# 6_-H3_MAIN.net
KiCad netlist of a schematic drawn in Altium Designer
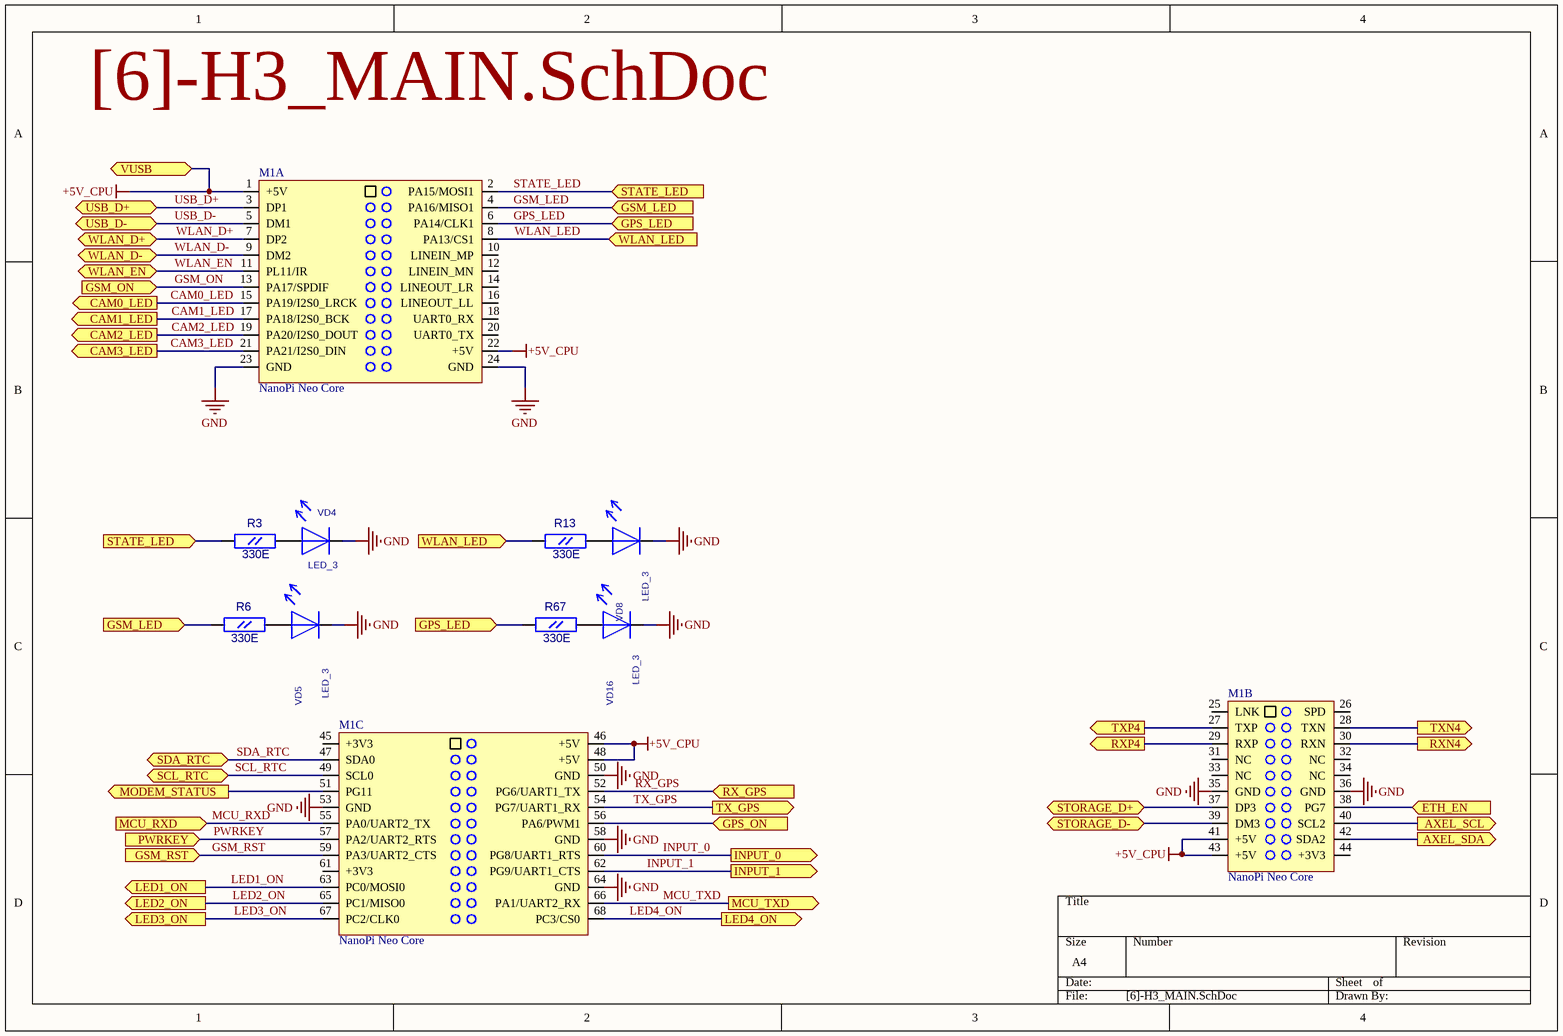
[diagram p0: [6]-H3_MAIN.SchDoc]

(export (version "E")
  (design (tool "Eeschema 10.0.6"))
  (components
    (comp (ref "M1")
      (value "NanoPi Neo Core")
      (footprint "NanoPiNeo_CORE")
      (description "Nano Pi Neo Core Allwinner H3 based embedded module")
      (libsource (lib "fizik_lib") (part "NanoPi Neo Core"))
    )
    (comp (ref "R3")
      (value "330E")
      (footprint "RC0603")
      (description "RC0603")
      (libsource (lib "fizik_lib (1)") (part "RC0603"))
    )
    (comp (ref "R6")
      (value "330E")
      (footprint "RC0603")
      (description "RC0603")
      (libsource (lib "fizik_lib (1)") (part "RC0603"))
    )
    (comp (ref "R13")
      (value "330E")
      (footprint "RC0603")
      (description "RC0603")
      (libsource (lib "fizik_lib (1)") (part "RC0603"))
    )
    (comp (ref "R67")
      (value "330E")
      (footprint "RC0603")
      (description "RC0603")
      (libsource (lib "fizik_lib (1)") (part "RC0603"))
    )
    (comp (ref "VD4") (value "LED_3") (footprint "LED3") (libsource (lib "fizik_lib (1)") (part "LED_3")))
    (comp (ref "VD5") (value "LED_3") (footprint "LED3") (libsource (lib "fizik_lib (1)") (part "LED_3")))
    (comp (ref "VD8") (value "LED_3") (footprint "LED3") (libsource (lib "fizik_lib (1)") (part "LED_3")))
    (comp (ref "VD16") (value "LED_3") (footprint "LED3") (libsource (lib "fizik_lib (1)") (part "LED_3")))
  )
  (nets
    (net (code "1") (name "+5V_CPU") (class "Default")
      (node (ref "M1") (pin "1") (pinfunction "+5V_1") (pintype "passive"))
      (node (ref "M1") (pin "22") (pinfunction "+5V_22") (pintype "passive"))
      (node (ref "M1") (pin "41") (pinfunction "+5V_41") (pintype "passive"))
      (node (ref "M1") (pin "43") (pinfunction "+5V_43") (pintype "passive"))
      (node (ref "M1") (pin "46") (pinfunction "+5V_46") (pintype "passive"))
      (node (ref "M1") (pin "48") (pinfunction "+5V_48") (pintype "passive"))
    )
    (net (code "2") (name "/AXEL_SCL") (class "Default")
      (node (ref "M1") (pin "40") (pinfunction "SCL2_40") (pintype "passive"))
    )
    (net (code "3") (name "/AXEL_SDA") (class "Default")
      (node (ref "M1") (pin "42") (pinfunction "SDA2_42") (pintype "passive"))
    )
    (net (code "4") (name "/CAM0_LED") (class "Default")
      (node (ref "M1") (pin "15") (pinfunction "PA19/I2S0_LRCK_15") (pintype "passive"))
    )
    (net (code "5") (name "/CAM1_LED") (class "Default")
      (node (ref "M1") (pin "17") (pinfunction "PA18/I2S0_BCK_17") (pintype "passive"))
    )
    (net (code "6") (name "/CAM2_LED") (class "Default")
      (node (ref "M1") (pin "19") (pinfunction "PA20/I2S0_DOUT_19") (pintype "passive"))
    )
    (net (code "7") (name "/CAM3_LED") (class "Default")
      (node (ref "M1") (pin "21") (pinfunction "PA21/I2S0_DIN_21") (pintype "passive"))
    )
    (net (code "8") (name "/ETH_EN") (class "Default")
      (node (ref "M1") (pin "38") (pinfunction "PG7_38") (pintype "passive"))
    )
    (net (code "9") (name "/GPS_LED") (class "Default")
      (node (ref "M1") (pin "6") (pinfunction "PA14/CLK1_6") (pintype "passive"))
      (node (ref "R67") (pin "1") (pinfunction "A_1") (pintype "passive"))
    )
    (net (code "10") (name "/GPS_ON") (class "Default")
      (node (ref "M1") (pin "56") (pinfunction "PA6/PWM1_56") (pintype "passive"))
    )
    (net (code "11") (name "/GSM_LED") (class "Default")
      (node (ref "M1") (pin "4") (pinfunction "PA16/MISO1_4") (pintype "passive"))
      (node (ref "R6") (pin "1") (pinfunction "A_1") (pintype "passive"))
    )
    (net (code "12") (name "/GSM_ON") (class "Default")
      (node (ref "M1") (pin "13") (pinfunction "PA17/SPDIF_13") (pintype "passive"))
    )
    (net (code "13") (name "/GSM_RST") (class "Default")
      (node (ref "M1") (pin "59") (pinfunction "PA3/UART2_CTS_59") (pintype "passive"))
    )
    (net (code "14") (name "/INPUT_0") (class "Default")
      (node (ref "M1") (pin "60") (pinfunction "PG8/UART1_RTS_60") (pintype "passive"))
    )
    (net (code "15") (name "/INPUT_1") (class "Default")
      (node (ref "M1") (pin "62") (pinfunction "PG9/UART1_CTS_62") (pintype "passive"))
    )
    (net (code "16") (name "/LED1_ON") (class "Default")
      (node (ref "M1") (pin "63") (pinfunction "PC0/MOSI0_63") (pintype "passive"))
    )
    (net (code "17") (name "/LED2_ON") (class "Default")
      (node (ref "M1") (pin "65") (pinfunction "PC1/MISO0_65") (pintype "passive"))
    )
    (net (code "18") (name "/LED3_ON") (class "Default")
      (node (ref "M1") (pin "67") (pinfunction "PC2/CLK0_67") (pintype "passive"))
    )
    (net (code "19") (name "/LED4_ON") (class "Default")
      (node (ref "M1") (pin "68") (pinfunction "PC3/CS0_68") (pintype "passive"))
    )
    (net (code "20") (name "/MCU_RXD") (class "Default")
      (node (ref "M1") (pin "55") (pinfunction "PA0/UART2_TX_55") (pintype "passive"))
    )
    (net (code "21") (name "/MCU_TXD") (class "Default")
      (node (ref "M1") (pin "66") (pinfunction "PA1/UART2_RX_66") (pintype "passive"))
    )
    (net (code "22") (name "/MODEM_STATUS") (class "Default")
      (node (ref "M1") (pin "51") (pinfunction "PG11_51") (pintype "passive"))
    )
    (net (code "23") (name "/PWRKEY") (class "Default")
      (node (ref "M1") (pin "57") (pinfunction "PA2/UART2_RTS_57") (pintype "passive"))
    )
    (net (code "24") (name "/RXN4") (class "Default")
      (node (ref "M1") (pin "30") (pinfunction "RXN_30") (pintype "passive"))
    )
    (net (code "25") (name "/RXP4") (class "Default")
      (node (ref "M1") (pin "29") (pinfunction "RXP_29") (pintype "passive"))
    )
    (net (code "26") (name "/RX_GPS") (class "Default")
      (node (ref "M1") (pin "52") (pinfunction "PG6/UART1_TX_52") (pintype "passive"))
    )
    (net (code "27") (name "/SCL_RTC") (class "Default")
      (node (ref "M1") (pin "49") (pinfunction "SCL0_49") (pintype "passive"))
    )
    (net (code "28") (name "/SDA_RTC") (class "Default")
      (node (ref "M1") (pin "47") (pinfunction "SDA0_47") (pintype "passive"))
    )
    (net (code "29") (name "/STATE_LED") (class "Default")
      (node (ref "M1") (pin "2") (pinfunction "PA15/MOSI1_2") (pintype "passive"))
      (node (ref "R3") (pin "1") (pinfunction "A_1") (pintype "passive"))
    )
    (net (code "30") (name "/STORAGE_D+") (class "Default")
      (node (ref "M1") (pin "37") (pinfunction "DP3_37") (pintype "passive"))
    )
    (net (code "31") (name "/STORAGE_D-") (class "Default")
      (node (ref "M1") (pin "39") (pinfunction "DM3_39") (pintype "passive"))
    )
    (net (code "32") (name "/TXN4") (class "Default")
      (node (ref "M1") (pin "28") (pinfunction "TXN_28") (pintype "passive"))
    )
    (net (code "33") (name "/TXP4") (class "Default")
      (node (ref "M1") (pin "27") (pinfunction "TXP_27") (pintype "passive"))
    )
    (net (code "34") (name "/TX_GPS") (class "Default")
      (node (ref "M1") (pin "54") (pinfunction "PG7/UART1_RX_54") (pintype "passive"))
    )
    (net (code "35") (name "/USB_D+") (class "Default")
      (node (ref "M1") (pin "3") (pinfunction "DP1_3") (pintype "passive"))
    )
    (net (code "36") (name "/USB_D-") (class "Default")
      (node (ref "M1") (pin "5") (pinfunction "DM1_5") (pintype "passive"))
    )
    (net (code "37") (name "/WLAN_D+") (class "Default")
      (node (ref "M1") (pin "7") (pinfunction "DP2_7") (pintype "passive"))
    )
    (net (code "38") (name "/WLAN_D-") (class "Default")
      (node (ref "M1") (pin "9") (pinfunction "DM2_9") (pintype "passive"))
    )
    (net (code "39") (name "/WLAN_EN") (class "Default")
      (node (ref "M1") (pin "11") (pinfunction "PL11/IR_11") (pintype "passive"))
    )
    (net (code "40") (name "/WLAN_LED") (class "Default")
      (node (ref "M1") (pin "8") (pinfunction "PA13/CS1_8") (pintype "passive"))
      (node (ref "R13") (pin "1") (pinfunction "A_1") (pintype "passive"))
    )
    (net (code "41") (name "GND") (class "Default")
      (node (ref "M1") (pin "23") (pinfunction "GND_23") (pintype "passive"))
      (node (ref "M1") (pin "24") (pinfunction "GND_24") (pintype "passive"))
      (node (ref "M1") (pin "35") (pinfunction "GND_35") (pintype "passive"))
      (node (ref "M1") (pin "36") (pinfunction "GND_36") (pintype "passive"))
      (node (ref "M1") (pin "50") (pinfunction "GND_50") (pintype "passive"))
      (node (ref "M1") (pin "53") (pinfunction "GND_53") (pintype "passive"))
      (node (ref "M1") (pin "58") (pinfunction "GND_58") (pintype "passive"))
      (node (ref "M1") (pin "64") (pinfunction "GND_64") (pintype "passive"))
      (node (ref "VD16") (pin "1") (pintype "passive"))
      (node (ref "VD4") (pin "1") (pintype "passive"))
      (node (ref "VD5") (pin "1") (pintype "passive"))
      (node (ref "VD8") (pin "1") (pintype "passive"))
    )
    (net (code "42") (name "Net-(R3-B)") (class "Default")
      (node (ref "R3") (pin "2") (pinfunction "B_2") (pintype "passive"))
      (node (ref "VD4") (pin "2") (pintype "passive"))
    )
    (net (code "43") (name "Net-(R6-B)") (class "Default")
      (node (ref "R6") (pin "2") (pinfunction "B_2") (pintype "passive"))
      (node (ref "VD5") (pin "2") (pintype "passive"))
    )
    (net (code "44") (name "Net-(R13-B)") (class "Default")
      (node (ref "R13") (pin "2") (pinfunction "B_2") (pintype "passive"))
      (node (ref "VD8") (pin "2") (pintype "passive"))
    )
    (net (code "45") (name "Net-(R67-B)") (class "Default")
      (node (ref "R67") (pin "2") (pinfunction "B_2") (pintype "passive"))
      (node (ref "VD16") (pin "2") (pintype "passive"))
    )
    (net (code "46") (name "unconnected-(M1A-LINEIN_MN-Pad12)") (class "Default")
      (node (ref "M1") (pin "12") (pinfunction "LINEIN_MN_12") (pintype "passive"))
    )
    (net (code "47") (name "unconnected-(M1A-LINEIN_MP-Pad10)") (class "Default")
      (node (ref "M1") (pin "10") (pinfunction "LINEIN_MP_10") (pintype "passive"))
    )
    (net (code "48") (name "unconnected-(M1A-LINEOUT_LL-Pad16)") (class "Default")
      (node (ref "M1") (pin "16") (pinfunction "LINEOUT_LL_16") (pintype "passive"))
    )
    (net (code "49") (name "unconnected-(M1A-LINEOUT_LR-Pad14)") (class "Default")
      (node (ref "M1") (pin "14") (pinfunction "LINEOUT_LR_14") (pintype "passive"))
    )
    (net (code "50") (name "unconnected-(M1A-UART0_RX-Pad18)") (class "Default")
      (node (ref "M1") (pin "18") (pinfunction "UART0_RX_18") (pintype "passive"))
    )
    (net (code "51") (name "unconnected-(M1A-UART0_TX-Pad20)") (class "Default")
      (node (ref "M1") (pin "20") (pinfunction "UART0_TX_20") (pintype "passive"))
    )
    (net (code "52") (name "unconnected-(M1B-+3V3-Pad44)") (class "Default")
      (node (ref "M1") (pin "44") (pinfunction "+3V3_44") (pintype "passive"))
    )
    (net (code "53") (name "unconnected-(M1B-LNK-Pad25)") (class "Default")
      (node (ref "M1") (pin "25") (pinfunction "LNK_25") (pintype "passive"))
    )
    (net (code "54") (name "unconnected-(M1B-NC-Pad31)") (class "Default")
      (node (ref "M1") (pin "31") (pinfunction "NC_31") (pintype "passive"))
    )
    (net (code "55") (name "unconnected-(M1B-NC-Pad32)") (class "Default")
      (node (ref "M1") (pin "32") (pinfunction "NC_32") (pintype "passive"))
    )
    (net (code "56") (name "unconnected-(M1B-NC-Pad33)") (class "Default")
      (node (ref "M1") (pin "33") (pinfunction "NC_33") (pintype "passive"))
    )
    (net (code "57") (name "unconnected-(M1B-NC-Pad34)") (class "Default")
      (node (ref "M1") (pin "34") (pinfunction "NC_34") (pintype "passive"))
    )
    (net (code "58") (name "unconnected-(M1B-SPD-Pad26)") (class "Default")
      (node (ref "M1") (pin "26") (pinfunction "SPD_26") (pintype "passive"))
    )
    (net (code "59") (name "unconnected-(M1C-+3V3-Pad45)") (class "Default")
      (node (ref "M1") (pin "45") (pinfunction "+3V3_45") (pintype "passive"))
    )
    (net (code "60") (name "unconnected-(M1C-+3V3-Pad61)") (class "Default")
      (node (ref "M1") (pin "61") (pinfunction "+3V3_61") (pintype "passive"))
    )
  )
)
